# P06_DEBUG_UART_RTC_WD.net
KiCad netlist of a schematic drawn in Altium Designer
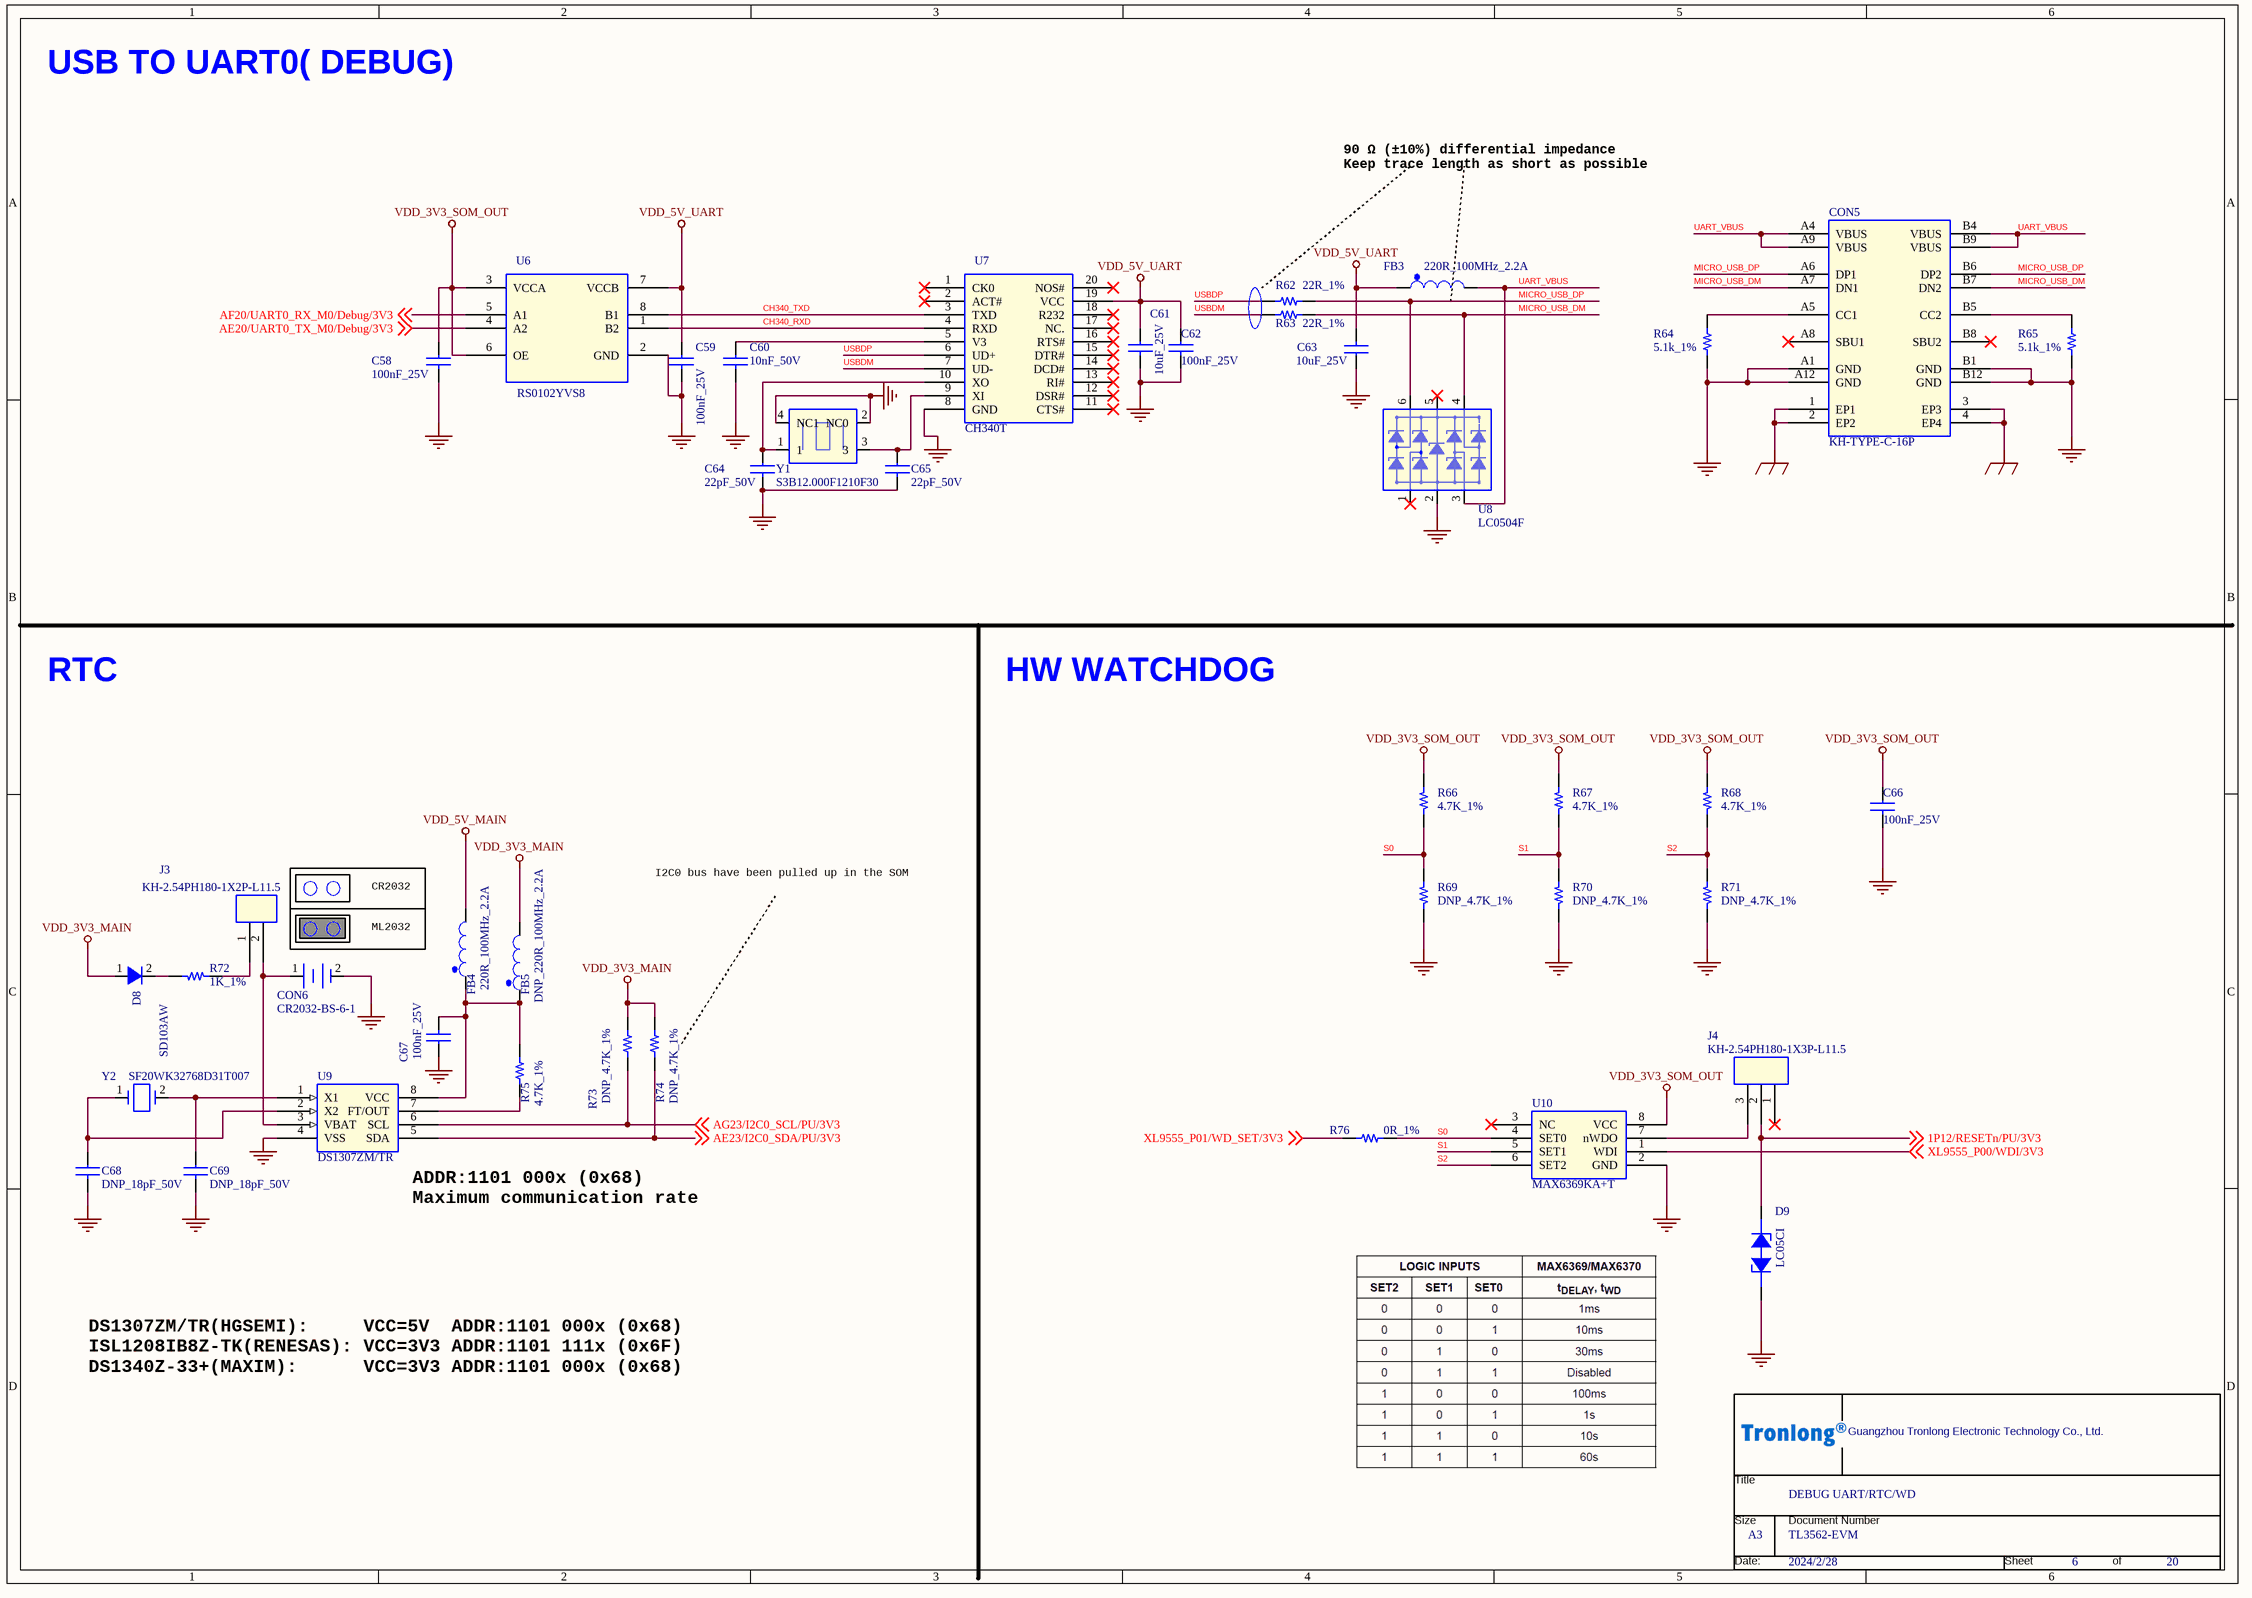
[diagram p0: P06_DEBUG UART_RTC_WD.SchDoc]

(export (version "E")
  (design (tool "Eeschema 10.0.6"))
  (components
    (comp (ref "C58")
      (value "100nF_25V")
      (footprint "C0402")
      (description "贴片陶瓷电容,100nF,10%,25V,X5R")
      (libsource (lib "*") (part "CAP NP_Dup3"))
    )
    (comp (ref "C59")
      (value "100nF_25V")
      (footprint "C0402")
      (description "贴片陶瓷电容,100nF,10%,25V,X5R")
      (libsource (lib "*") (part "CAP NP_Dup3"))
    )
    (comp (ref "C60")
      (value "10nF_50V")
      (footprint "C0402")
      (description "贴片陶瓷电容,10nF,10%,50V,X7R")
      (libsource (lib "*") (part "CAP NP_Dup3"))
    )
    (comp (ref "C61")
      (value "10uF_25V")
      (footprint "C0603")
      (description "贴片陶瓷电容,10uF,10%,10V,X5R")
      (libsource (lib "*") (part "CAP NP_Dup3"))
    )
    (comp (ref "C62")
      (value "100nF_25V")
      (footprint "C0402")
      (description "贴片陶瓷电容,100nF,10%,25V,X5R")
      (libsource (lib "*") (part "CAP NP_Dup3"))
    )
    (comp (ref "C63")
      (value "10uF_25V")
      (footprint "C0603")
      (description "贴片陶瓷电容,10uF,10%,10V,X5R")
      (libsource (lib "*") (part "CAP NP_Dup3"))
    )
    (comp (ref "C64")
      (value "22pF_50V")
      (footprint "C0603")
      (description "贴片陶瓷电容,22pF,5%,50V,C0G")
      (libsource (lib "*") (part "CAP NP_Dup3"))
    )
    (comp (ref "C65")
      (value "22pF_50V")
      (footprint "C0603")
      (description "贴片陶瓷电容,22pF,5%,50V,C0G")
      (libsource (lib "*") (part "CAP NP_Dup3"))
    )
    (comp (ref "C66")
      (value "100nF_25V")
      (footprint "C0402")
      (description "贴片陶瓷电容,100nF,10%,25V,X5R")
      (libsource (lib "*") (part "CAP NP_Dup3"))
    )
    (comp (ref "C67")
      (value "100nF_25V")
      (footprint "C0402")
      (description "贴片陶瓷电容,100nF,10%,25V,X5R")
      (libsource (lib "*") (part "CAP NP_Dup3"))
    )
    (comp (ref "C68")
      (value "DNP_18pF_50V")
      (footprint "C0603")
      (description "贴片陶瓷电容,18pF,5%,50V,C0G")
      (libsource (lib "*") (part "CAP NP_Dup3"))
    )
    (comp (ref "C69")
      (value "DNP_18pF_50V")
      (footprint "C0603")
      (description "贴片陶瓷电容,18pF,5%,50V,C0G")
      (libsource (lib "*") (part "CAP NP_Dup3"))
    )
    (comp (ref "CON5")
      (value "KH-TYPE-C-16P")
      (footprint "TYPE-C_16P_90_SMD")
      (description "Type-C 母座 90度 16 Pin")
      (fields (field (name "MANUFACTURER") "深圳市金航标电子有限公司(kinghelm)"))
      (libsource (lib "*") (part "usb 3_0.0 type-c female"))
    )
    (comp (ref "CON6")
      (value "CR2032-BS-6-1")
      (footprint "CON_BATTERY_CR2032")
      (description "2032,纽扣电池座,2PIN,180度,白色,卧式,贴片")
      (fields (field (name "MANUFACTURER") "深圳市琦捷电子有限公司（Q&J）"))
      (libsource (lib "*") (part "BATTERY"))
    )
    (comp (ref "D8")
      (value "SD103AW")
      (footprint "SOD-123_NEW")
      (description "肖特基二极管,VR=40V,IF=350mA,VF=0.37V@20mA,trr=10ns")
      (fields (field (name "TIINTPARTNUMBER") "1E0013") (field (name "MFR") "On Semiconductor"))
      (libsource (lib "TL3562-EVM-A1-0-000-D-20231116") (part "Diode200mA250V_1"))
    )
    (comp (ref "D9")
      (value "LC05CI")
      (footprint "SOD323_BI")
      (description "TVS二极管,VRWM=5V,VBR=6V,一组,双向,30KV,30KV")
      (fields
        (field (name "MANUFACTURER PART NUMBER") "PESD3V3L1BA")
        (field (name "MANUFACTURER") "上海雷卯电子科技有限公司（Leiditech）")
      )
      (libsource (lib "*") (part "DIODE BREAKDOWN_2"))
    )
    (comp (ref "FB3")
      (value "220R_100MHz_2.2A")
      (footprint "L0603")
      (description "磁珠,50mΩ,2.2A,220R@100MHz")
      (fields
        (field (name "MANUFACTURER") "深圳顺络电子股份有限公司（Sunlord）")
        (field (name "MANUFACTURER PARTNUMBER") "UPZ1608U221-2R2TF")
      )
      (libsource (lib "*") (part "FERRITE BEAD_Dup2"))
    )
    (comp (ref "FB4")
      (value "220R_100MHz_2.2A")
      (footprint "L0603")
      (description "磁珠,50mΩ,2.2A,220R@100MHz")
      (fields
        (field (name "MANUFACTURER PARTNUMBER") "UPZ1608U221-2R2TF")
        (field (name "MANUFACTURER") "深圳顺络电子股份有限公司（Sunlord）")
      )
      (libsource (lib "*") (part "FERRITE BEAD_Dup2"))
    )
    (comp (ref "FB5")
      (value "DNP_220R_100MHz_2.2A")
      (footprint "L0603")
      (description "磁珠,50mΩ,2.2A,220R@100MHz")
      (fields
        (field (name "MANUFACTURER PARTNUMBER") "UPZ1608U221-2R2TF")
        (field (name "MANUFACTURER") "深圳顺络电子股份有限公司（Sunlord）")
      )
      (libsource (lib "*") (part "FERRITE BEAD_Dup2"))
    )
    (comp (ref "J3")
      (value "KH-2.54PH180-1X2P-L11.5")
      (footprint "header_1x2p_2d54_male")
      (description "排针,1x2PIN,间距2.54MM,180度,黑色,插件")
      (fields (field (name "MANUFACTURER") "深圳市金航标电子有限公司(kinghelm)"))
      (libsource (lib "*") (part "CON2_0"))
    )
    (comp (ref "J4")
      (value "KH-2.54PH180-1X3P-L11.5")
      (footprint "CON3_2D254")
      (description "排针,1x3PIN,间距2.54MM,180度,黑色,插件")
      (fields (field (name "MANUFACTURER") "深圳市金航标电子有限公司(kinghelm)"))
      (libsource (lib "*") (part "CON3_Dup2"))
    )
    (comp (ref "R62")
      (value "22R_1%")
      (footprint "R0402")
      (description "贴片电阻,22R,±1%,1/16W")
      (libsource (lib "*") (part "Resistor_Dup3"))
    )
    (comp (ref "R63")
      (value "22R_1%")
      (footprint "R0402")
      (description "贴片电阻,22R,±1%,1/16W")
      (libsource (lib "*") (part "Resistor_Dup3"))
    )
    (comp (ref "R64")
      (value "5.1k_1%")
      (footprint "R0402")
      (description "贴片电阻,5.1K,±1%,1/16W")
      (libsource (lib "*") (part "Resistor_Dup3"))
    )
    (comp (ref "R65")
      (value "5.1k_1%")
      (footprint "R0402")
      (description "贴片电阻,5.1K,±1%,1/16W")
      (libsource (lib "*") (part "Resistor_Dup3"))
    )
    (comp (ref "R66")
      (value "4.7K_1%")
      (footprint "R0402")
      (description "贴片电阻,4.7K,±1%,1/16W")
      (libsource (lib "*") (part "Resistor_Dup3"))
    )
    (comp (ref "R67")
      (value "4.7K_1%")
      (footprint "R0402")
      (description "贴片电阻,4.7K,±1%,1/16W")
      (libsource (lib "*") (part "Resistor_Dup3"))
    )
    (comp (ref "R68")
      (value "4.7K_1%")
      (footprint "R0402")
      (description "贴片电阻,4.7K,±1%,1/16W")
      (libsource (lib "*") (part "Resistor_Dup3"))
    )
    (comp (ref "R69")
      (value "DNP_4.7K_1%")
      (footprint "R0402")
      (description "贴片电阻,4.7K,±1%,1/16W")
      (libsource (lib "*") (part "Resistor_Dup3"))
    )
    (comp (ref "R70")
      (value "DNP_4.7K_1%")
      (footprint "R0402")
      (description "贴片电阻,4.7K,±1%,1/16W")
      (libsource (lib "*") (part "Resistor_Dup3"))
    )
    (comp (ref "R71")
      (value "DNP_4.7K_1%")
      (footprint "R0402")
      (description "贴片电阻,4.7K,±1%,1/16W")
      (libsource (lib "*") (part "Resistor_Dup3"))
    )
    (comp (ref "R72")
      (value "1K_1%")
      (footprint "R0402")
      (description "贴片电阻,1K,±1%,1/16W")
      (libsource (lib "*") (part "Resistor_Dup3"))
    )
    (comp (ref "R73")
      (value "DNP_4.7K_1%")
      (footprint "R0402")
      (description "贴片电阻,4.7K,±1%,1/16W")
      (libsource (lib "*") (part "Resistor_Dup3"))
    )
    (comp (ref "R74")
      (value "DNP_4.7K_1%")
      (footprint "R0402")
      (description "贴片电阻,4.7K,±1%,1/16W")
      (libsource (lib "*") (part "Resistor_Dup3"))
    )
    (comp (ref "R75")
      (value "4.7K_1%")
      (footprint "R0402")
      (description "贴片电阻,4.7K,±1%,1/16W")
      (libsource (lib "*") (part "Resistor_Dup3"))
    )
    (comp (ref "R76")
      (value "0R_1%")
      (footprint "R0402")
      (description "0R,±1%,R0402,≥1/16W")
      (libsource (lib "*") (part "Resistor_Dup3"))
    )
    (comp (ref "U6")
      (value "RS0102YVS8")
      (footprint "SOP8-20-91")
      (description "2位双向电平转换器")
      (fields (field (name "MANUFACTURER") "江苏润石科技有限公司（RUNIC）"))
      (libsource (lib "*") (part "TXS0102DCUR"))
    )
    (comp (ref "U7")
      (value "CH340T")
      (footprint "TSSOP-20")
      (description "USB转UART芯片")
      (fields (field (name "MANUFACTURER") "南京沁恒微电子股份有限公司（WCH）"))
      (libsource (lib "TL3562-EVM-A1-0-000-D-20231116") (part "CH340T"))
    )
    (comp (ref "U8")
      (value "LC0504F")
      (footprint "SOT363")
      (description "ESD二极管,VRWM=5V,VBR=6V,四组,单向,8KV,15KV")
      (fields
        (field (name "MANUFACTURER PART NUMBER") "PRTR5V0U4Y")
        (field (name "MANUFACTURER") "上海雷卯电子科技有限公司（Leiditech）")
      )
      (libsource (lib "*") (part "PRTR5V0U4Y_0"))
    )
    (comp (ref "U9")
      (value "DS1307ZM/TR")
      (footprint "SOIC8_D8")
      (description "RTC芯片")
      (fields (field (name "MANUFACTURER") "广东华冠半导体有限公司（HGSEMI）"))
      (libsource (lib "*") (part "IC_MCP79410_0"))
    )
    (comp (ref "U10")
      (value "MAX6369KA+T")
      (footprint "sot23_8")
      (description "低电平有效开漏输出,2.5V-5.5V,-40~125℃")
      (fields (field (name "MANUFACTURER") "Maxim Integrated（美国美信）"))
      (libsource (lib "*") (part "MAX637x"))
    )
    (comp (ref "Y1")
      (value "S3B12.000F1210F30")
      (footprint "SMD_3225")
      (description "四脚无源晶振,12MHz,±10ppm,12pF,100Ω,±30ppm")
      (fields (field (name "MANUFACTURER") "深圳市星通时频电子有限公司公司（JSCJ）"))
      (libsource (lib "*") (part "CRYSTAL"))
    )
    (comp (ref "Y2")
      (value "SF20WK32768D31T007")
      (footprint "SMD_2012")
      (description "两脚无源晶振,32.768KHz,±20ppm,12.5pF,80KΩ,±20ppm")
      (fields (field (name "MFR") "Epson") (field (name "TIINTPARTNUMBER") "1Y0029"))
      (libsource (lib "TL3562-EVM-A1-0-000-D-20231116") (part "CRYS_32_768KHz_SMD"))
    )
  )
  (nets
    (net (code "1") (name "/CH340_RXD") (class "Default")
      (node (ref "U6") (pin "1") (pinfunction "B2_1") (pintype "passive"))
      (node (ref "U7") (pin "4") (pinfunction "RXD_4") (pintype "passive"))
    )
    (net (code "2") (name "/CH340_TXD") (class "Default")
      (node (ref "U6") (pin "8") (pinfunction "B1_8") (pintype "passive"))
      (node (ref "U7") (pin "3") (pinfunction "TXD_3") (pintype "passive"))
    )
    (net (code "3") (name "/MICRO_USB_DM") (class "Default")
      (node (ref "CON5") (pin "A7") (pinfunction "DN1_A7") (pintype "passive"))
      (node (ref "CON5") (pin "B7") (pinfunction "DN2_B7") (pintype "passive"))
      (node (ref "R63") (pin "2") (pinfunction "2_2") (pintype "passive"))
      (node (ref "U8") (pin "4") (pinfunction "4_4") (pintype "passive"))
    )
    (net (code "4") (name "/MICRO_USB_DP") (class "Default")
      (node (ref "CON5") (pin "A6") (pinfunction "DP1_A6") (pintype "passive"))
      (node (ref "CON5") (pin "B6") (pinfunction "DP2_B6") (pintype "passive"))
      (node (ref "R62") (pin "2") (pinfunction "2_2") (pintype "passive"))
      (node (ref "U8") (pin "6") (pinfunction "6_6") (pintype "passive"))
    )
    (net (code "5") (name "/S0") (class "Default")
      (node (ref "R66") (pin "2") (pinfunction "2_2") (pintype "passive"))
      (node (ref "R69") (pin "1") (pinfunction "1_1") (pintype "passive"))
      (node (ref "R76") (pin "1") (pinfunction "1_1") (pintype "passive"))
      (node (ref "U10") (pin "4") (pinfunction "SET0_4") (pintype "passive"))
    )
    (net (code "6") (name "/S1") (class "Default")
      (node (ref "R67") (pin "2") (pinfunction "2_2") (pintype "passive"))
      (node (ref "R70") (pin "1") (pinfunction "1_1") (pintype "passive"))
      (node (ref "U10") (pin "5") (pinfunction "SET1_5") (pintype "passive"))
    )
    (net (code "7") (name "/S2") (class "Default")
      (node (ref "R68") (pin "2") (pinfunction "2_2") (pintype "passive"))
      (node (ref "R71") (pin "1") (pinfunction "1_1") (pintype "passive"))
      (node (ref "U10") (pin "6") (pinfunction "SET2_6") (pintype "passive"))
    )
    (net (code "8") (name "/UART_VBUS") (class "Default")
      (node (ref "CON5") (pin "A4") (pinfunction "VBUS_A4") (pintype "power_in"))
      (node (ref "CON5") (pin "A9") (pinfunction "VBUS_A9") (pintype "power_in"))
      (node (ref "CON5") (pin "B4") (pinfunction "VBUS_B4") (pintype "power_in"))
      (node (ref "CON5") (pin "B9") (pinfunction "VBUS_B9") (pintype "power_in"))
      (node (ref "FB3") (pin "2") (pinfunction "2_2") (pintype "passive"))
      (node (ref "U8") (pin "3") (pinfunction "3_3") (pintype "passive"))
    )
    (net (code "9") (name "/USBDM") (class "Default")
      (node (ref "R63") (pin "1") (pinfunction "1_1") (pintype "passive"))
      (node (ref "U7") (pin "7") (pinfunction "UD-_7") (pintype "passive"))
    )
    (net (code "10") (name "/USBDP") (class "Default")
      (node (ref "R62") (pin "1") (pinfunction "1_1") (pintype "passive"))
      (node (ref "U7") (pin "6") (pinfunction "UD+_6") (pintype "passive"))
    )
    (net (code "11") (name "1P12{slash}RESETn{slash}PU{slash}3V3") (class "Default")
      (node (ref "D9") (pin "1") (pinfunction "ANODE1_1") (pintype "passive"))
      (node (ref "J4") (pin "2") (pinfunction "2_2") (pintype "passive"))
    )
    (net (code "12") (name "AE20{slash}UART0_TX_M0{slash}Debug{slash}3V3") (class "Default")
      (node (ref "U6") (pin "4") (pinfunction "A2_4") (pintype "passive"))
    )
    (net (code "13") (name "AE23{slash}I2C0_SDA{slash}PU{slash}3V3") (class "Default")
      (node (ref "R74") (pin "2") (pinfunction "2_2") (pintype "passive"))
      (node (ref "U9") (pin "5") (pinfunction "SDA_5") (pintype "passive"))
    )
    (net (code "14") (name "AF20{slash}UART0_RX_M0{slash}Debug{slash}3V3") (class "Default")
      (node (ref "U6") (pin "5") (pinfunction "A1_5") (pintype "passive"))
    )
    (net (code "15") (name "AG23{slash}I2C0_SCL{slash}PU{slash}3V3") (class "Default")
      (node (ref "R73") (pin "2") (pinfunction "2_2") (pintype "passive"))
      (node (ref "U9") (pin "6") (pinfunction "SCL_6") (pintype "passive"))
    )
    (net (code "16") (name "EGND") (class "Default")
      (node (ref "CON5") (pin "1") (pinfunction "EP1_1") (pintype "power_in"))
      (node (ref "CON5") (pin "2") (pinfunction "EP2_2") (pintype "power_in"))
      (node (ref "CON5") (pin "3") (pinfunction "EP3_3") (pintype "power_in"))
      (node (ref "CON5") (pin "4") (pinfunction "EP4_4") (pintype "power_in"))
    )
    (net (code "17") (name "GND") (class "Default")
      (node (ref "C58") (pin "2") (pinfunction "2_2") (pintype "passive"))
      (node (ref "C59") (pin "2") (pinfunction "2_2") (pintype "passive"))
      (node (ref "C60") (pin "2") (pinfunction "2_2") (pintype "passive"))
      (node (ref "C61") (pin "2") (pinfunction "2_2") (pintype "passive"))
      (node (ref "C62") (pin "2") (pinfunction "2_2") (pintype "passive"))
      (node (ref "C63") (pin "1") (pinfunction "1_1") (pintype "passive"))
      (node (ref "C64") (pin "2") (pinfunction "2_2") (pintype "passive"))
      (node (ref "C65") (pin "2") (pinfunction "2_2") (pintype "passive"))
      (node (ref "C66") (pin "2") (pinfunction "2_2") (pintype "passive"))
      (node (ref "C67") (pin "1") (pinfunction "1_1") (pintype "passive"))
      (node (ref "C68") (pin "2") (pinfunction "2_2") (pintype "passive"))
      (node (ref "C69") (pin "2") (pinfunction "2_2") (pintype "passive"))
      (node (ref "CON5") (pin "A1") (pinfunction "GND_A1") (pintype "power_in"))
      (node (ref "CON5") (pin "A12") (pinfunction "GND_A12") (pintype "power_in"))
      (node (ref "CON5") (pin "B1") (pinfunction "GND_B1") (pintype "power_in"))
      (node (ref "CON5") (pin "B12") (pinfunction "GND_B12") (pintype "power_in"))
      (node (ref "CON6") (pin "2") (pinfunction "-_2") (pintype "passive"))
      (node (ref "D9") (pin "2") (pinfunction "CATHODE2_2") (pintype "passive"))
      (node (ref "R64") (pin "2") (pinfunction "2_2") (pintype "passive"))
      (node (ref "R65") (pin "2") (pinfunction "2_2") (pintype "passive"))
      (node (ref "R69") (pin "2") (pinfunction "2_2") (pintype "passive"))
      (node (ref "R70") (pin "2") (pinfunction "2_2") (pintype "passive"))
      (node (ref "R71") (pin "2") (pinfunction "2_2") (pintype "passive"))
      (node (ref "U10") (pin "2") (pinfunction "GND_2") (pintype "passive"))
      (node (ref "U6") (pin "2") (pinfunction "GND_2") (pintype "passive"))
      (node (ref "U7") (pin "8") (pinfunction "GND_8") (pintype "passive"))
      (node (ref "U8") (pin "2") (pinfunction "2_2") (pintype "passive"))
      (node (ref "U9") (pin "4") (pinfunction "VSS_4") (pintype "power_in"))
      (node (ref "Y1") (pin "2") (pinfunction "NC0_2") (pintype "passive"))
      (node (ref "Y1") (pin "4") (pinfunction "NC1_4") (pintype "passive"))
    )
    (net (code "18") (name "Net-(CON5-CC1)") (class "Default")
      (node (ref "CON5") (pin "A5") (pinfunction "CC1_A5") (pintype "passive"))
      (node (ref "R64") (pin "1") (pinfunction "1_1") (pintype "passive"))
    )
    (net (code "19") (name "Net-(CON5-CC2)") (class "Default")
      (node (ref "CON5") (pin "B5") (pinfunction "CC2_B5") (pintype "passive"))
      (node (ref "R65") (pin "1") (pinfunction "1_1") (pintype "passive"))
    )
    (net (code "20") (name "Net-(CON6-+)") (class "Default")
      (node (ref "CON6") (pin "1") (pinfunction "+_1") (pintype "passive"))
      (node (ref "J3") (pin "2") (pinfunction "2_2") (pintype "passive"))
      (node (ref "U9") (pin "3") (pinfunction "VBAT_3") (pintype "input"))
    )
    (net (code "21") (name "Net-(D8-Cathode)") (class "Default")
      (node (ref "D8") (pin "2") (pinfunction "Cathode_2") (pintype "passive"))
      (node (ref "R72") (pin "2") (pinfunction "2_2") (pintype "passive"))
    )
    (net (code "22") (name "Net-(J3-Pad1)") (class "Default")
      (node (ref "J3") (pin "1") (pinfunction "1_1") (pintype "passive"))
      (node (ref "R72") (pin "1") (pinfunction "1_1") (pintype "passive"))
    )
    (net (code "23") (name "Net-(U7-V3)") (class "Default")
      (node (ref "C60") (pin "1") (pinfunction "1_1") (pintype "passive"))
      (node (ref "U7") (pin "5") (pinfunction "V3_5") (pintype "passive"))
    )
    (net (code "24") (name "Net-(U7-XI)") (class "Default")
      (node (ref "C65") (pin "1") (pinfunction "1_1") (pintype "passive"))
      (node (ref "U7") (pin "9") (pinfunction "XI_9") (pintype "passive"))
      (node (ref "Y1") (pin "3") (pinfunction "3_3") (pintype "passive"))
    )
    (net (code "25") (name "Net-(U7-XO)") (class "Default")
      (node (ref "C64") (pin "1") (pinfunction "1_1") (pintype "passive"))
      (node (ref "U7") (pin "10") (pinfunction "XO_10") (pintype "passive"))
      (node (ref "Y1") (pin "1") (pinfunction "1_1") (pintype "passive"))
    )
    (net (code "26") (name "Net-(U9-FT{slash}OUT)") (class "Default")
      (node (ref "R75") (pin "2") (pinfunction "2_2") (pintype "passive"))
      (node (ref "U9") (pin "7") (pinfunction "FT/OUT_7") (pintype "passive"))
    )
    (net (code "27") (name "Net-(U9-VCC)") (class "Default")
      (node (ref "C67") (pin "2") (pinfunction "2_2") (pintype "passive"))
      (node (ref "FB4") (pin "1") (pinfunction "1_1") (pintype "passive"))
      (node (ref "FB5") (pin "1") (pinfunction "1_1") (pintype "passive"))
      (node (ref "R75") (pin "1") (pinfunction "1_1") (pintype "passive"))
      (node (ref "U9") (pin "8") (pinfunction "VCC_8") (pintype "power_in"))
    )
    (net (code "28") (name "Net-(U9-X1)") (class "Default")
      (node (ref "C69") (pin "1") (pinfunction "1_1") (pintype "passive"))
      (node (ref "U9") (pin "1") (pinfunction "X1_1") (pintype "input"))
      (node (ref "Y2") (pin "2") (pinfunction "2_2") (pintype "passive"))
    )
    (net (code "29") (name "Net-(U9-X2)") (class "Default")
      (node (ref "C68") (pin "1") (pinfunction "1_1") (pintype "passive"))
      (node (ref "U9") (pin "2") (pinfunction "X2_2") (pintype "input"))
      (node (ref "Y2") (pin "1") (pinfunction "1_1") (pintype "passive"))
    )
    (net (code "30") (name "Net-(U10-nWDO)") (class "Default")
      (node (ref "J4") (pin "3") (pinfunction "3_3") (pintype "passive"))
      (node (ref "U10") (pin "7") (pinfunction "nWDO_7") (pintype "passive"))
    )
    (net (code "31") (name "VDD_3V3_MAIN") (class "Default")
      (node (ref "D8") (pin "1") (pinfunction "Anode_1") (pintype "passive"))
      (node (ref "FB5") (pin "2") (pinfunction "2_2") (pintype "passive"))
      (node (ref "R73") (pin "1") (pinfunction "1_1") (pintype "passive"))
      (node (ref "R74") (pin "1") (pinfunction "1_1") (pintype "passive"))
    )
    (net (code "32") (name "VDD_3V3_SOM_OUT") (class "Default")
      (node (ref "C58") (pin "1") (pinfunction "1_1") (pintype "passive"))
      (node (ref "C66") (pin "1") (pinfunction "1_1") (pintype "passive"))
      (node (ref "R66") (pin "1") (pinfunction "1_1") (pintype "passive"))
      (node (ref "R67") (pin "1") (pinfunction "1_1") (pintype "passive"))
      (node (ref "R68") (pin "1") (pinfunction "1_1") (pintype "passive"))
      (node (ref "U10") (pin "8") (pinfunction "VCC_8") (pintype "passive"))
      (node (ref "U6") (pin "3") (pinfunction "VCCA_3") (pintype "passive"))
      (node (ref "U6") (pin "6") (pinfunction "OE_6") (pintype "passive"))
    )
    (net (code "33") (name "VDD_5V_MAIN") (class "Default")
      (node (ref "FB4") (pin "2") (pinfunction "2_2") (pintype "passive"))
    )
    (net (code "34") (name "VDD_5V_UART") (class "Default")
      (node (ref "C59") (pin "1") (pinfunction "1_1") (pintype "passive"))
      (node (ref "C61") (pin "1") (pinfunction "1_1") (pintype "passive"))
      (node (ref "C62") (pin "1") (pinfunction "1_1") (pintype "passive"))
      (node (ref "C63") (pin "2") (pinfunction "2_2") (pintype "passive"))
      (node (ref "FB3") (pin "1") (pinfunction "1_1") (pintype "passive"))
      (node (ref "U6") (pin "7") (pinfunction "VCCB_7") (pintype "passive"))
      (node (ref "U7") (pin "19") (pinfunction "VCC_19") (pintype "passive"))
    )
    (net (code "35") (name "XL9555_P00{slash}WDI{slash}3V3") (class "Default")
      (node (ref "U10") (pin "1") (pinfunction "WDI_1") (pintype "passive"))
    )
    (net (code "36") (name "XL9555_P01{slash}WD_SET{slash}3V3") (class "Default")
      (node (ref "R76") (pin "2") (pinfunction "2_2") (pintype "passive"))
    )
    (net (code "37") (name "unconnected-(CON5-SBU1-PadA8)") (class "Default")
      (node (ref "CON5") (pin "A8") (pinfunction "SBU1_A8") (pintype "passive+no_connect"))
    )
    (net (code "38") (name "unconnected-(CON5-SBU2-PadB8)") (class "Default")
      (node (ref "CON5") (pin "B8") (pinfunction "SBU2_B8") (pintype "passive+no_connect"))
    )
    (net (code "39") (name "unconnected-(J4-Pad1)") (class "Default")
      (node (ref "J4") (pin "1") (pinfunction "1_1") (pintype "passive+no_connect"))
    )
    (net (code "40") (name "unconnected-(U7-ACT#-Pad2)") (class "Default")
      (node (ref "U7") (pin "2") (pinfunction "ACT#_2") (pintype "passive+no_connect"))
    )
    (net (code "41") (name "unconnected-(U7-CK0-Pad1)") (class "Default")
      (node (ref "U7") (pin "1") (pinfunction "CK0_1") (pintype "passive+no_connect"))
    )
    (net (code "42") (name "unconnected-(U7-CTS#-Pad11)") (class "Default")
      (node (ref "U7") (pin "11") (pinfunction "CTS#_11") (pintype "passive+no_connect"))
    )
    (net (code "43") (name "unconnected-(U7-DCD#-Pad14)") (class "Default")
      (node (ref "U7") (pin "14") (pinfunction "DCD#_14") (pintype "passive+no_connect"))
    )
    (net (code "44") (name "unconnected-(U7-DSR#-Pad12)") (class "Default")
      (node (ref "U7") (pin "12") (pinfunction "DSR#_12") (pintype "passive+no_connect"))
    )
    (net (code "45") (name "unconnected-(U7-DTR#-Pad15)") (class "Default")
      (node (ref "U7") (pin "15") (pinfunction "DTR#_15") (pintype "passive+no_connect"))
    )
    (net (code "46") (name "unconnected-(U7-NC.-Pad17)") (class "Default")
      (node (ref "U7") (pin "17") (pinfunction "NC._17") (pintype "passive+no_connect"))
    )
    (net (code "47") (name "unconnected-(U7-NOS#-Pad20)") (class "Default")
      (node (ref "U7") (pin "20") (pinfunction "NOS#_20") (pintype "passive+no_connect"))
    )
    (net (code "48") (name "unconnected-(U7-R232-Pad18)") (class "Default")
      (node (ref "U7") (pin "18") (pinfunction "R232_18") (pintype "passive+no_connect"))
    )
    (net (code "49") (name "unconnected-(U7-RI#-Pad13)") (class "Default")
      (node (ref "U7") (pin "13") (pinfunction "RI#_13") (pintype "passive+no_connect"))
    )
    (net (code "50") (name "unconnected-(U7-RTS#-Pad16)") (class "Default")
      (node (ref "U7") (pin "16") (pinfunction "RTS#_16") (pintype "passive+no_connect"))
    )
    (net (code "51") (name "unconnected-(U8-Pad1)") (class "Default")
      (node (ref "U8") (pin "1") (pinfunction "1_1") (pintype "passive+no_connect"))
    )
    (net (code "52") (name "unconnected-(U8-Pad5)") (class "Default")
      (node (ref "U8") (pin "5") (pinfunction "5_5") (pintype "passive+no_connect"))
    )
    (net (code "53") (name "unconnected-(U10-NC-Pad3)") (class "Default")
      (node (ref "U10") (pin "3") (pinfunction "NC_3") (pintype "passive+no_connect"))
    )
  )
)
